# relays.net
KiCad netlist of a schematic drawn in EAGLE
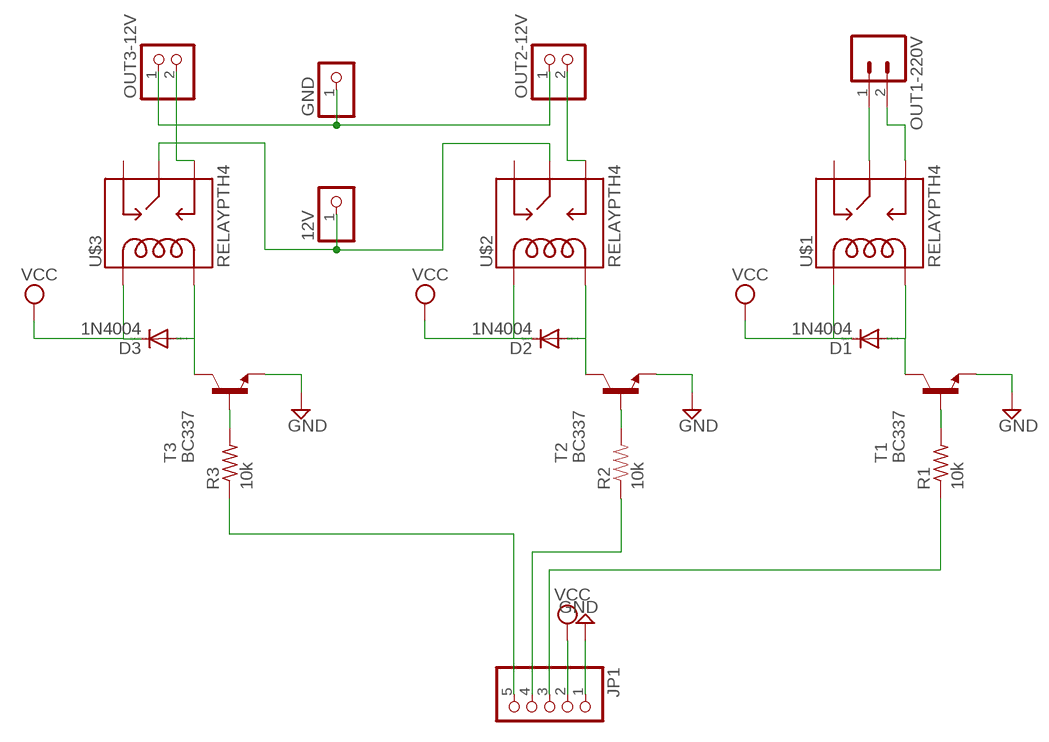
[diagram p0: schematic, sheet 1]

(export (version "E")
  (design (tool "Eeschema 10.0.6"))
  (components
    (comp (ref "12V")
      (value "PINHD-1X1")
      (footprint "eagle-import:1X01")
      (libsource (lib "eagle-import") (part "PINHD-1X1"))
    )
    (comp (ref "D1")
      (value "1N4004")
      (footprint "eagle-import:DO41-10")
      (libsource (lib "eagle-import") (part "1N4004"))
    )
    (comp (ref "D2")
      (value "1N4004")
      (footprint "eagle-import:DO41-10")
      (libsource (lib "eagle-import") (part "1N4004"))
    )
    (comp (ref "D3")
      (value "1N4004")
      (footprint "eagle-import:DO41-10")
      (libsource (lib "eagle-import") (part "1N4004"))
    )
    (comp (ref "GND")
      (value "PINHD-1X1")
      (footprint "eagle-import:1X01")
      (libsource (lib "eagle-import") (part "PINHD-1X1"))
    )
    (comp (ref "JP1")
      (value "PINHD-1X5")
      (footprint "eagle-import:1X05")
      (libsource (lib "eagle-import") (part "PINHD-1X5"))
    )
    (comp (ref "OUT1-220V")
      (value "M025MM")
      (footprint "eagle-import:SCREWTERMINAL-5MM-2")
      (libsource (lib "eagle-import") (part "M025MM"))
    )
    (comp (ref "OUT2-12V")
      (value "PINHD-1X2")
      (footprint "eagle-import:1X02")
      (libsource (lib "eagle-import") (part "PINHD-1X2"))
    )
    (comp (ref "OUT3-12V")
      (value "PINHD-1X2")
      (footprint "eagle-import:1X02")
      (libsource (lib "eagle-import") (part "PINHD-1X2"))
    )
    (comp (ref "R1")
      (value "10k")
      (footprint "eagle-import:0207_15")
      (libsource (lib "eagle-import") (part "R-US_0207/15"))
    )
    (comp (ref "R2")
      (value "10k")
      (footprint "eagle-import:AXIAL-0.1")
      (libsource (lib "eagle-import") (part "10KOHM-1/4W5%(PTH)VERT"))
    )
    (comp (ref "R3")
      (value "10k")
      (footprint "eagle-import:0207_15")
      (libsource (lib "eagle-import") (part "R-US_0207/15"))
    )
    (comp (ref "T1")
      (value "BC337")
      (footprint "eagle-import:TO92")
      (libsource (lib "eagle-import") (part "BC337"))
    )
    (comp (ref "T2")
      (value "BC337")
      (footprint "eagle-import:TO92")
      (libsource (lib "eagle-import") (part "BC337"))
    )
    (comp (ref "T3")
      (value "BC337")
      (footprint "eagle-import:TO92")
      (libsource (lib "eagle-import") (part "BC337"))
    )
    (comp (ref "U$1")
      (value "RELAYPTH4")
      (footprint "eagle-import:RELAY-JZC")
      (libsource (lib "eagle-import") (part "RELAYPTH4"))
    )
    (comp (ref "U$2")
      (value "RELAYPTH4")
      (footprint "eagle-import:RELAY-JZC")
      (libsource (lib "eagle-import") (part "RELAYPTH4"))
    )
    (comp (ref "U$3")
      (value "RELAYPTH4")
      (footprint "eagle-import:RELAY-JZC")
      (libsource (lib "eagle-import") (part "RELAYPTH4"))
    )
  )
  (nets
    (net (code "1") (name "GND") (class "Default")
      (node (ref "JP1") (pin "1") (pinfunction "1_1") (pintype "passive"))
      (node (ref "T1") (pin "1") (pinfunction "E_1") (pintype "passive"))
      (node (ref "T2") (pin "1") (pinfunction "E_1") (pintype "passive"))
      (node (ref "T3") (pin "1") (pinfunction "E_1") (pintype "passive"))
    )
    (net (code "2") (name "Net-(GND-Pad1)") (class "Default")
      (node (ref "GND") (pin "1") (pinfunction "1_1") (pintype "passive"))
      (node (ref "OUT2-12V") (pin "1") (pinfunction "1_1") (pintype "passive"))
      (node (ref "OUT3-12V") (pin "1") (pinfunction "1_1") (pintype "passive"))
    )
    (net (code "3") (name "Net-(JP1-Pad3)") (class "Default")
      (node (ref "JP1") (pin "3") (pinfunction "3_3") (pintype "passive"))
      (node (ref "R1") (pin "1") (pinfunction "1_1") (pintype "passive"))
    )
    (net (code "4") (name "Net-(JP1-Pad5)") (class "Default")
      (node (ref "JP1") (pin "5") (pinfunction "5_5") (pintype "passive"))
      (node (ref "R3") (pin "1") (pinfunction "1_1") (pintype "passive"))
    )
    (net (code "5") (name "Net-(R2-1)") (class "Default")
      (node (ref "JP1") (pin "4") (pinfunction "4_4") (pintype "passive"))
      (node (ref "R2") (pin "P$1") (pinfunction "1_P$1") (pintype "passive"))
    )
    (net (code "6") (name "Net-(R2-2)") (class "Default")
      (node (ref "R2") (pin "P$2") (pinfunction "2_P$2") (pintype "passive"))
      (node (ref "T2") (pin "2") (pinfunction "B_2") (pintype "passive"))
    )
    (net (code "7") (name "Net-(T1-B)") (class "Default")
      (node (ref "R1") (pin "2") (pinfunction "2_2") (pintype "passive"))
      (node (ref "T1") (pin "2") (pinfunction "B_2") (pintype "passive"))
    )
    (net (code "8") (name "Net-(T1-C)") (class "Default")
      (node (ref "D1") (pin "A") (pinfunction "A_A") (pintype "passive"))
      (node (ref "T1") (pin "3") (pinfunction "C_3") (pintype "passive"))
      (node (ref "U$1") (pin "1") (pinfunction "COIL2_1") (pintype "bidirectional"))
    )
    (net (code "9") (name "Net-(T2-C)") (class "Default")
      (node (ref "D2") (pin "A") (pinfunction "A_A") (pintype "passive"))
      (node (ref "T2") (pin "3") (pinfunction "C_3") (pintype "passive"))
      (node (ref "U$2") (pin "1") (pinfunction "COIL2_1") (pintype "bidirectional"))
    )
    (net (code "10") (name "Net-(T3-B)") (class "Default")
      (node (ref "R3") (pin "2") (pinfunction "2_2") (pintype "passive"))
      (node (ref "T3") (pin "2") (pinfunction "B_2") (pintype "passive"))
    )
    (net (code "11") (name "Net-(T3-C)") (class "Default")
      (node (ref "D3") (pin "A") (pinfunction "A_A") (pintype "passive"))
      (node (ref "T3") (pin "3") (pinfunction "C_3") (pintype "passive"))
      (node (ref "U$3") (pin "1") (pinfunction "COIL2_1") (pintype "bidirectional"))
    )
    (net (code "12") (name "Net-(U$1-MAIN)") (class "Default")
      (node (ref "OUT1-220V") (pin "1") (pinfunction "1_1") (pintype "passive"))
      (node (ref "U$1") (pin "4") (pinfunction "MAIN_4") (pintype "bidirectional"))
    )
    (net (code "13") (name "Net-(U$1-NO)") (class "Default")
      (node (ref "OUT1-220V") (pin "2") (pinfunction "2_2") (pintype "passive"))
      (node (ref "U$1") (pin "3") (pinfunction "NO_3") (pintype "bidirectional"))
    )
    (net (code "14") (name "Net-(U$2-MAIN)") (class "Default")
      (node (ref "12V") (pin "1") (pinfunction "1_1") (pintype "passive"))
      (node (ref "U$2") (pin "4") (pinfunction "MAIN_4") (pintype "bidirectional"))
      (node (ref "U$3") (pin "4") (pinfunction "MAIN_4") (pintype "bidirectional"))
    )
    (net (code "15") (name "Net-(U$2-NO)") (class "Default")
      (node (ref "OUT2-12V") (pin "2") (pinfunction "2_2") (pintype "passive"))
      (node (ref "U$2") (pin "3") (pinfunction "NO_3") (pintype "bidirectional"))
    )
    (net (code "16") (name "Net-(U$3-NO)") (class "Default")
      (node (ref "OUT3-12V") (pin "2") (pinfunction "2_2") (pintype "passive"))
      (node (ref "U$3") (pin "3") (pinfunction "NO_3") (pintype "bidirectional"))
    )
    (net (code "17") (name "VCC") (class "Default")
      (node (ref "D1") (pin "C") (pinfunction "C_C") (pintype "passive"))
      (node (ref "D2") (pin "C") (pinfunction "C_C") (pintype "passive"))
      (node (ref "D3") (pin "C") (pinfunction "C_C") (pintype "passive"))
      (node (ref "JP1") (pin "2") (pinfunction "2_2") (pintype "passive"))
      (node (ref "U$1") (pin "5") (pinfunction "COIL1_5") (pintype "bidirectional"))
      (node (ref "U$2") (pin "5") (pinfunction "COIL1_5") (pintype "bidirectional"))
      (node (ref "U$3") (pin "5") (pinfunction "COIL1_5") (pintype "bidirectional"))
    )
    (net (code "18") (name "unconnected-(U$1-NC-Pad2)") (class "Default")
      (node (ref "U$1") (pin "2") (pinfunction "NC_2") (pintype "bidirectional"))
    )
    (net (code "19") (name "unconnected-(U$2-NC-Pad2)") (class "Default")
      (node (ref "U$2") (pin "2") (pinfunction "NC_2") (pintype "bidirectional"))
    )
    (net (code "20") (name "unconnected-(U$3-NC-Pad2)") (class "Default")
      (node (ref "U$3") (pin "2") (pinfunction "NC_2") (pintype "bidirectional"))
    )
  )
)
